# cw-twostage.net
KiCad netlist of a schematic drawn in EAGLE
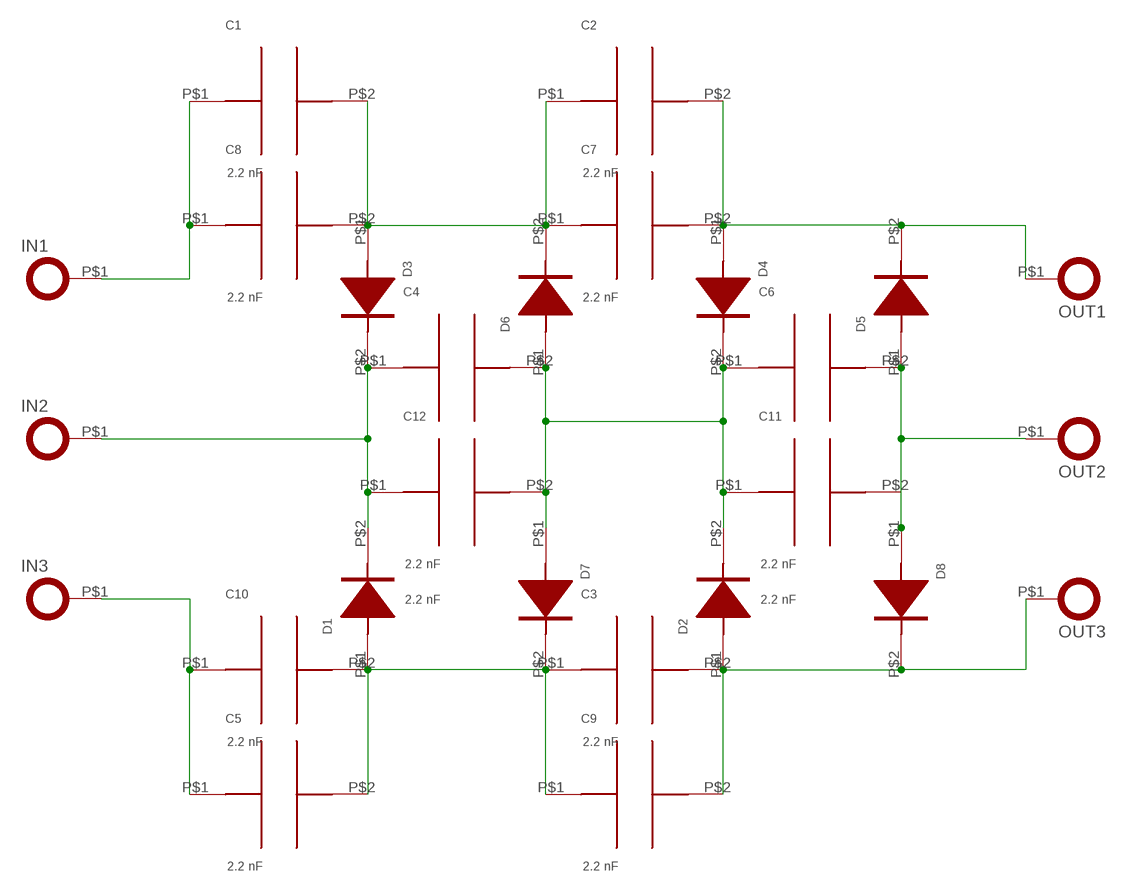
[diagram p0: schematic, sheet 1]

(export (version "E")
  (design (tool "Eeschema 10.0.6"))
  (components
    (comp (ref "C1")
      (value "2.2 nF")
      (footprint "eagle-import:CAP_CT81_12")
      (libsource (lib "eagle-import") (part "HV_CAPACITOR_12MM"))
    )
    (comp (ref "C2")
      (value "2.2 nF")
      (footprint "eagle-import:CAP_CT81_12")
      (libsource (lib "eagle-import") (part "HV_CAPACITOR_12MM"))
    )
    (comp (ref "C3")
      (value "2.2 nF")
      (footprint "eagle-import:CAP_CT81_12")
      (libsource (lib "eagle-import") (part "HV_CAPACITOR_12MM"))
    )
    (comp (ref "C4")
      (value "2.2 nF")
      (footprint "eagle-import:CAP_CT81_12")
      (libsource (lib "eagle-import") (part "HV_CAPACITOR_12MM"))
    )
    (comp (ref "C5")
      (value "2.2 nF")
      (footprint "eagle-import:CAP_CT81_12")
      (libsource (lib "eagle-import") (part "HV_CAPACITOR_12MM"))
    )
    (comp (ref "C6")
      (value "2.2 nF")
      (footprint "eagle-import:CAP_CT81_12")
      (libsource (lib "eagle-import") (part "HV_CAPACITOR_12MM"))
    )
    (comp (ref "C7")
      (value "2.2 nF")
      (footprint "eagle-import:CAP_CT81_12")
      (libsource (lib "eagle-import") (part "HV_CAPACITOR_12MM"))
    )
    (comp (ref "C8")
      (value "2.2 nF")
      (footprint "eagle-import:CAP_CT81_12")
      (libsource (lib "eagle-import") (part "HV_CAPACITOR_12MM"))
    )
    (comp (ref "C9")
      (value "2.2 nF")
      (footprint "eagle-import:CAP_CT81_12")
      (libsource (lib "eagle-import") (part "HV_CAPACITOR_12MM"))
    )
    (comp (ref "C10")
      (value "2.2 nF")
      (footprint "eagle-import:CAP_CT81_12")
      (libsource (lib "eagle-import") (part "HV_CAPACITOR_12MM"))
    )
    (comp (ref "C11")
      (value "2.2 nF")
      (footprint "eagle-import:CAP_CT81_12")
      (libsource (lib "eagle-import") (part "HV_CAPACITOR_12MM"))
    )
    (comp (ref "C12")
      (value "2.2 nF")
      (footprint "eagle-import:CAP_CT81_12")
      (libsource (lib "eagle-import") (part "HV_CAPACITOR_12MM"))
    )
    (comp (ref "D1")
      (value "DIODE_14MM")
      (footprint "eagle-import:DIODE_14")
      (libsource (lib "eagle-import") (part "DIODE_14MM"))
    )
    (comp (ref "D2")
      (value "DIODE_14MM")
      (footprint "eagle-import:DIODE_14")
      (libsource (lib "eagle-import") (part "DIODE_14MM"))
    )
    (comp (ref "D3")
      (value "DIODE_14MM")
      (footprint "eagle-import:DIODE_14")
      (libsource (lib "eagle-import") (part "DIODE_14MM"))
    )
    (comp (ref "D4")
      (value "DIODE_14MM")
      (footprint "eagle-import:DIODE_14")
      (libsource (lib "eagle-import") (part "DIODE_14MM"))
    )
    (comp (ref "D5")
      (value "DIODE_14MM")
      (footprint "eagle-import:DIODE_14")
      (libsource (lib "eagle-import") (part "DIODE_14MM"))
    )
    (comp (ref "D6")
      (value "DIODE_14MM")
      (footprint "eagle-import:DIODE_14")
      (libsource (lib "eagle-import") (part "DIODE_14MM"))
    )
    (comp (ref "D7")
      (value "DIODE_14MM")
      (footprint "eagle-import:DIODE_14")
      (libsource (lib "eagle-import") (part "DIODE_14MM"))
    )
    (comp (ref "D8")
      (value "DIODE_14MM")
      (footprint "eagle-import:DIODE_14")
      (libsource (lib "eagle-import") (part "DIODE_14MM"))
    )
    (comp (ref "IN1")
      (value "TERMINAL_M6")
      (footprint "eagle-import:LUG_SQUARE_M6")
      (libsource (lib "eagle-import") (part "TERMINAL_M6"))
    )
    (comp (ref "IN2")
      (value "TERMINAL_M6")
      (footprint "eagle-import:LUG_SQUARE_M6")
      (libsource (lib "eagle-import") (part "TERMINAL_M6"))
    )
    (comp (ref "IN3")
      (value "TERMINAL_M6")
      (footprint "eagle-import:LUG_SQUARE_M6")
      (libsource (lib "eagle-import") (part "TERMINAL_M6"))
    )
    (comp (ref "OUT1")
      (value "TERMINAL_M6")
      (footprint "eagle-import:LUG_SQUARE_M6")
      (libsource (lib "eagle-import") (part "TERMINAL_M6"))
    )
    (comp (ref "OUT2")
      (value "TERMINAL_M6")
      (footprint "eagle-import:LUG_SQUARE_M6")
      (libsource (lib "eagle-import") (part "TERMINAL_M6"))
    )
    (comp (ref "OUT3")
      (value "TERMINAL_M6")
      (footprint "eagle-import:LUG_SQUARE_M6")
      (libsource (lib "eagle-import") (part "TERMINAL_M6"))
    )
  )
  (nets
    (net (code "1") (name "Net-(C1-PadP$1)") (class "Default")
      (node (ref "C1") (pin "P$1") (pinfunction "P$1_P$1") (pintype "passive"))
      (node (ref "C8") (pin "P$1") (pinfunction "P$1_P$1") (pintype "passive"))
      (node (ref "IN1") (pin "P$1") (pinfunction "P$1_P$1") (pintype "passive"))
    )
    (net (code "2") (name "Net-(C10-PadP$1)") (class "Default")
      (node (ref "C10") (pin "P$1") (pinfunction "P$1_P$1") (pintype "passive"))
      (node (ref "C5") (pin "P$1") (pinfunction "P$1_P$1") (pintype "passive"))
      (node (ref "IN3") (pin "P$1") (pinfunction "P$1_P$1") (pintype "passive"))
    )
    (net (code "3") (name "Net-(D1-ANODE)") (class "Default")
      (node (ref "C10") (pin "P$2") (pinfunction "P$2_P$2") (pintype "passive"))
      (node (ref "C3") (pin "P$1") (pinfunction "P$1_P$1") (pintype "passive"))
      (node (ref "C5") (pin "P$2") (pinfunction "P$2_P$2") (pintype "passive"))
      (node (ref "C9") (pin "P$1") (pinfunction "P$1_P$1") (pintype "passive"))
      (node (ref "D1") (pin "P$1") (pinfunction "ANODE_P$1") (pintype "passive"))
      (node (ref "D7") (pin "P$2") (pinfunction "CATHODE_P$2") (pintype "passive"))
    )
    (net (code "4") (name "Net-(D1-CATHODE)") (class "Default")
      (node (ref "C12") (pin "P$1") (pinfunction "P$1_P$1") (pintype "passive"))
      (node (ref "C4") (pin "P$1") (pinfunction "P$1_P$1") (pintype "passive"))
      (node (ref "D1") (pin "P$2") (pinfunction "CATHODE_P$2") (pintype "passive"))
      (node (ref "D3") (pin "P$2") (pinfunction "CATHODE_P$2") (pintype "passive"))
      (node (ref "IN2") (pin "P$1") (pinfunction "P$1_P$1") (pintype "passive"))
    )
    (net (code "5") (name "Net-(D2-ANODE)") (class "Default")
      (node (ref "C3") (pin "P$2") (pinfunction "P$2_P$2") (pintype "passive"))
      (node (ref "C9") (pin "P$2") (pinfunction "P$2_P$2") (pintype "passive"))
      (node (ref "D2") (pin "P$1") (pinfunction "ANODE_P$1") (pintype "passive"))
      (node (ref "D8") (pin "P$2") (pinfunction "CATHODE_P$2") (pintype "passive"))
      (node (ref "OUT3") (pin "P$1") (pinfunction "P$1_P$1") (pintype "passive"))
    )
    (net (code "6") (name "Net-(D2-CATHODE)") (class "Default")
      (node (ref "C11") (pin "P$1") (pinfunction "P$1_P$1") (pintype "passive"))
      (node (ref "C12") (pin "P$2") (pinfunction "P$2_P$2") (pintype "passive"))
      (node (ref "C4") (pin "P$2") (pinfunction "P$2_P$2") (pintype "passive"))
      (node (ref "C6") (pin "P$1") (pinfunction "P$1_P$1") (pintype "passive"))
      (node (ref "D2") (pin "P$2") (pinfunction "CATHODE_P$2") (pintype "passive"))
      (node (ref "D4") (pin "P$2") (pinfunction "CATHODE_P$2") (pintype "passive"))
      (node (ref "D6") (pin "P$1") (pinfunction "ANODE_P$1") (pintype "passive"))
      (node (ref "D7") (pin "P$1") (pinfunction "ANODE_P$1") (pintype "passive"))
    )
    (net (code "7") (name "Net-(D3-ANODE)") (class "Default")
      (node (ref "C1") (pin "P$2") (pinfunction "P$2_P$2") (pintype "passive"))
      (node (ref "C2") (pin "P$1") (pinfunction "P$1_P$1") (pintype "passive"))
      (node (ref "C7") (pin "P$1") (pinfunction "P$1_P$1") (pintype "passive"))
      (node (ref "C8") (pin "P$2") (pinfunction "P$2_P$2") (pintype "passive"))
      (node (ref "D3") (pin "P$1") (pinfunction "ANODE_P$1") (pintype "passive"))
      (node (ref "D6") (pin "P$2") (pinfunction "CATHODE_P$2") (pintype "passive"))
    )
    (net (code "8") (name "Net-(D4-ANODE)") (class "Default")
      (node (ref "C2") (pin "P$2") (pinfunction "P$2_P$2") (pintype "passive"))
      (node (ref "C7") (pin "P$2") (pinfunction "P$2_P$2") (pintype "passive"))
      (node (ref "D4") (pin "P$1") (pinfunction "ANODE_P$1") (pintype "passive"))
      (node (ref "D5") (pin "P$2") (pinfunction "CATHODE_P$2") (pintype "passive"))
      (node (ref "OUT1") (pin "P$1") (pinfunction "P$1_P$1") (pintype "passive"))
    )
    (net (code "9") (name "Net-(D5-ANODE)") (class "Default")
      (node (ref "C11") (pin "P$2") (pinfunction "P$2_P$2") (pintype "passive"))
      (node (ref "C6") (pin "P$2") (pinfunction "P$2_P$2") (pintype "passive"))
      (node (ref "D5") (pin "P$1") (pinfunction "ANODE_P$1") (pintype "passive"))
      (node (ref "D8") (pin "P$1") (pinfunction "ANODE_P$1") (pintype "passive"))
      (node (ref "OUT2") (pin "P$1") (pinfunction "P$1_P$1") (pintype "passive"))
    )
  )
)
